# 1_81_Greyscale_OLED_Breakout.net
KiCad netlist of a schematic drawn in EAGLE
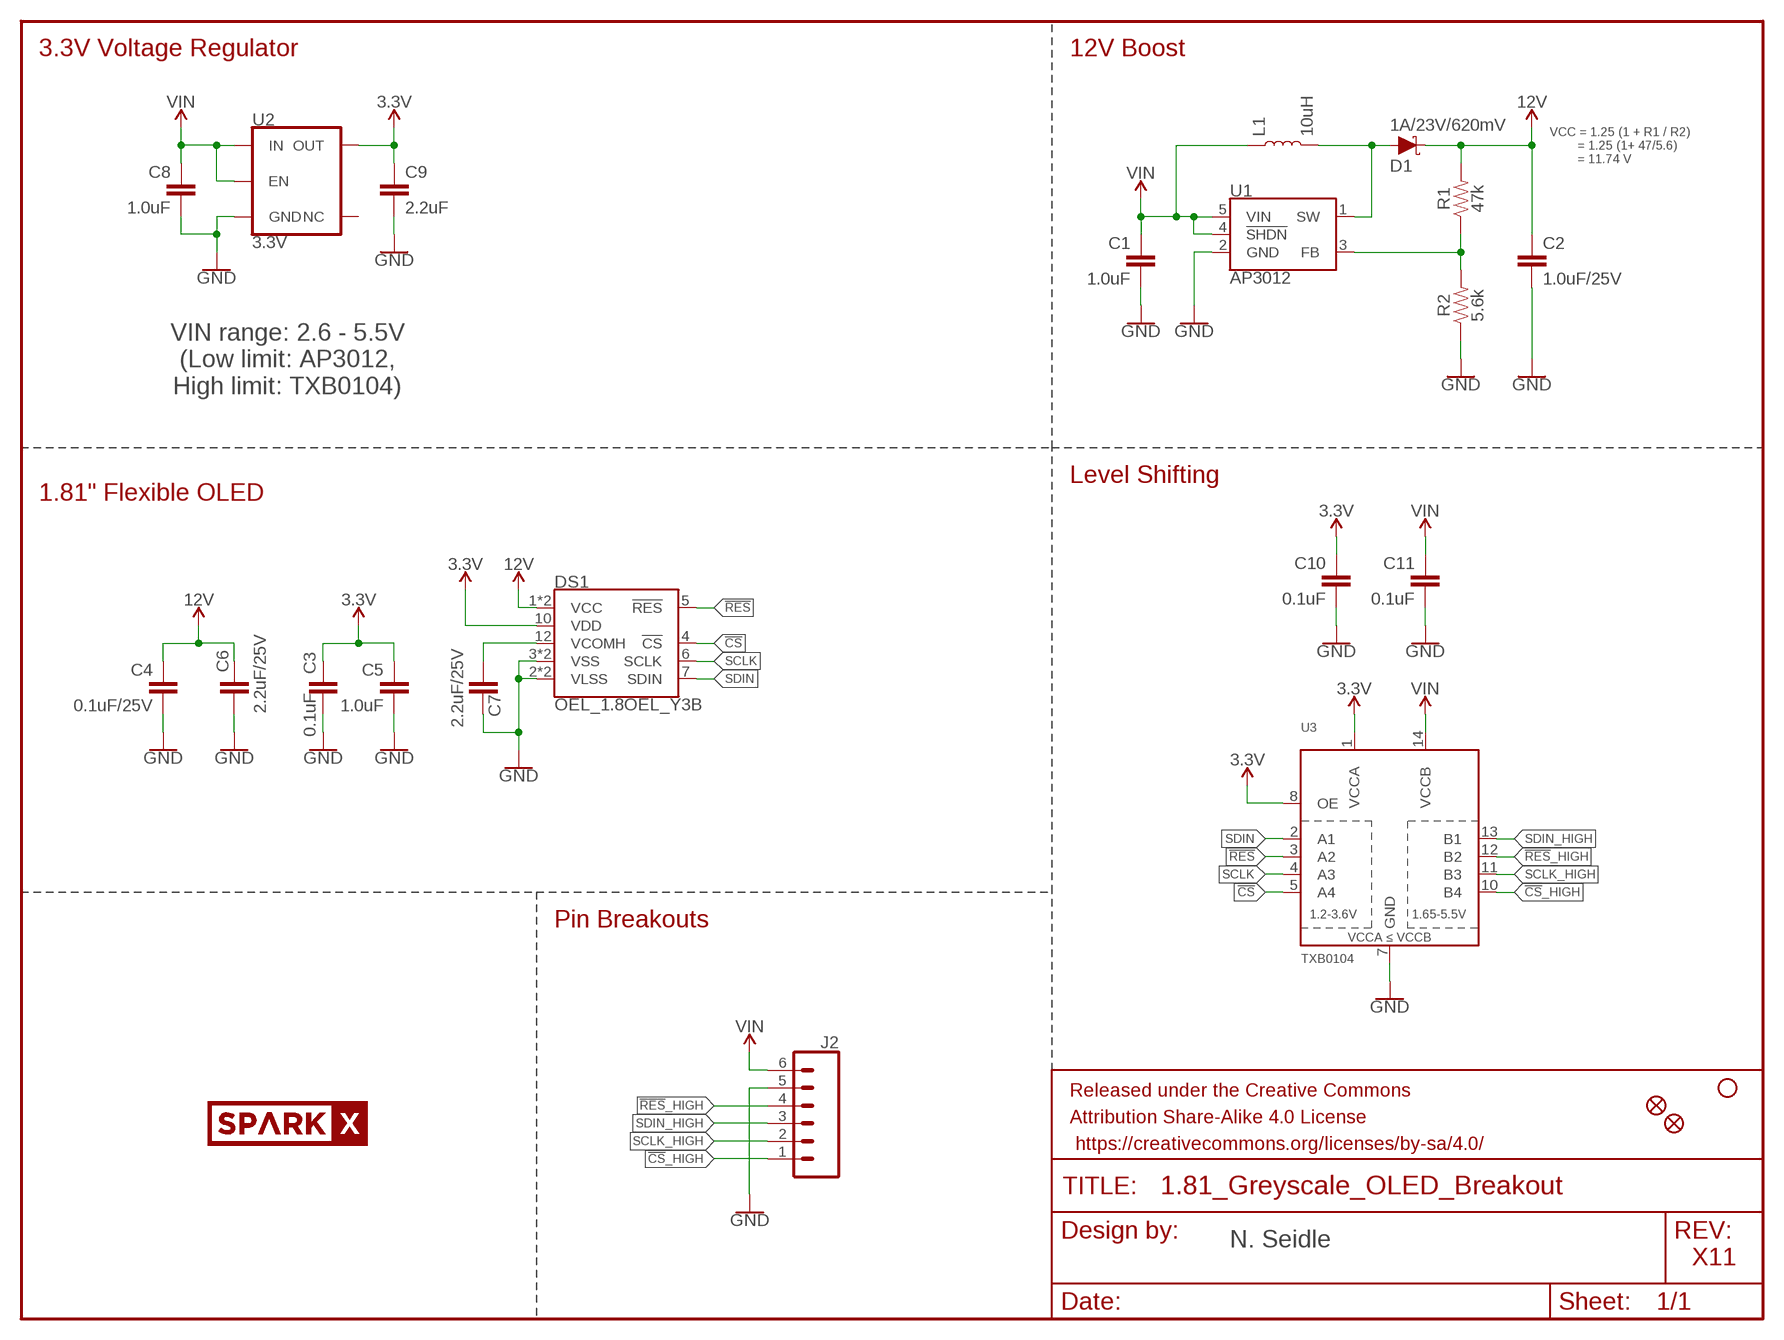
[diagram p0: schematic, sheet 1]

(export (version "E")
  (design (tool "Eeschema 10.0.6"))
  (components
    (comp (ref "C1")
      (value "1.0uF")
      (footprint "eagle-import:0603")
      (libsource (lib "eagle-import") (part "1.0UF-0603-16V-10%"))
    )
    (comp (ref "C2")
      (value "1.0uF/25V")
      (footprint "eagle-import:0805")
      (libsource (lib "eagle-import") (part "1.0UF-0805-25V-(+80/-20%)"))
    )
    (comp (ref "C3")
      (value "0.1uF")
      (footprint "eagle-import:0603")
      (libsource (lib "eagle-import") (part "0.1UF-0603-25V-(+80/-20%)"))
    )
    (comp (ref "C4")
      (value "0.1uF/25V")
      (footprint "eagle-import:0603")
      (libsource (lib "eagle-import") (part "0.1UF-0603-25V-(+80/-20%)"))
    )
    (comp (ref "C5")
      (value "1.0uF")
      (footprint "eagle-import:0603")
      (libsource (lib "eagle-import") (part "1.0UF-0603-16V-10%"))
    )
    (comp (ref "C6")
      (value "2.2uF/25V")
      (footprint "eagle-import:0805")
      (libsource (lib "eagle-import") (part "2.2UF-0805-25V-(+80/-20%)"))
    )
    (comp (ref "C7")
      (value "2.2uF/25V")
      (footprint "eagle-import:0805")
      (libsource (lib "eagle-import") (part "2.2UF-0805-25V-(+80/-20%)"))
    )
    (comp (ref "C8")
      (value "1.0uF")
      (footprint "eagle-import:0603")
      (libsource (lib "eagle-import") (part "1.0UF-0603-16V-10%"))
    )
    (comp (ref "C9")
      (value "2.2uF")
      (footprint "eagle-import:0603")
      (libsource (lib "eagle-import") (part "2.2UF-0603-10V-20%"))
    )
    (comp (ref "C10")
      (value "0.1uF")
      (footprint "eagle-import:0603")
      (libsource (lib "eagle-import") (part "0.1UF-0603-25V-(+80/-20%)"))
    )
    (comp (ref "C11")
      (value "0.1uF")
      (footprint "eagle-import:0603")
      (libsource (lib "eagle-import") (part "0.1UF-0603-25V-(+80/-20%)"))
    )
    (comp (ref "D1")
      (value "1A/23V/620mV")
      (footprint "eagle-import:SOD-323")
      (libsource (lib "eagle-import") (part "DIODE-SCHOTTKY-BAT20J"))
    )
    (comp (ref "DS1")
      (value "OEL_1.8OEL_Y3B")
      (footprint "eagle-import:OEL_1.8_FPC_Y3B")
      (libsource (lib "eagle-import") (part "OEL_1.8OEL_Y3B"))
    )
    (comp (ref "FD1")
      (value "FIDUCIAL1X2")
      (footprint "eagle-import:FIDUCIAL-1X2")
      (libsource (lib "eagle-import") (part "FIDUCIAL1X2"))
    )
    (comp (ref "FD2")
      (value "FIDUCIAL1X2")
      (footprint "eagle-import:FIDUCIAL-1X2")
      (libsource (lib "eagle-import") (part "FIDUCIAL1X2"))
    )
    (comp (ref "FRAME1")
      (value "FRAME-LETTER")
      (footprint "eagle-import:CREATIVE_COMMONS")
      (libsource (lib "eagle-import") (part "FRAME-LETTER"))
    )
    (comp (ref "H2")
      (value "STAND-OFF")
      (footprint "eagle-import:STAND-OFF")
      (libsource (lib "eagle-import") (part "STAND-OFF"))
    )
    (comp (ref "J2")
      (value "CONN_06NO_SILK_NO_POP")
      (footprint "eagle-import:1X06_NO_SILK")
      (libsource (lib "eagle-import") (part "CONN_06NO_SILK_NO_POP"))
    )
    (comp (ref "L1")
      (value "10uH")
      (footprint "eagle-import:INDUCTOR_3X3")
      (libsource (lib "eagle-import") (part "INDUCTORINDUCTOR_10UH"))
    )
    (comp (ref "LOGO1")
      (value "SPARKX-LOGO5")
      (footprint "eagle-import:SPARKX-LARGE")
      (libsource (lib "eagle-import") (part "SPARKX-LOGO5"))
    )
    (comp (ref "R1")
      (value "47k")
      (footprint "eagle-import:0603")
      (libsource (lib "eagle-import") (part "47KOHM-0603-1/10W-1%"))
    )
    (comp (ref "R2")
      (value "5.6k")
      (footprint "eagle-import:0603")
      (libsource (lib "eagle-import") (part "5.6KOHM-0603-1/10W-1%"))
    )
    (comp (ref "U1")
      (value "AP3012")
      (footprint "eagle-import:SOT23-5")
      (libsource (lib "eagle-import") (part "AP3012"))
    )
    (comp (ref "U2")
      (value "3.3V")
      (footprint "eagle-import:SOT23-5")
      (libsource (lib "eagle-import") (part "V_REG_AP2112K-3.3V"))
    )
    (comp (ref "U3")
      (value "TXB0104")
      (footprint "eagle-import:SO14")
      (libsource (lib "eagle-import") (part "TXB0104PWRSOIC14"))
    )
  )
  (nets
    (net (code "1") (name "/~{CS}") (class "Default")
      (node (ref "DS1") (pin "4") (pinfunction "~{CS}_4") (pintype "bidirectional"))
      (node (ref "U3") (pin "5") (pinfunction "A4_5") (pintype "bidirectional"))
    )
    (net (code "2") (name "/~{CS}_HIGH") (class "Default")
      (node (ref "J2") (pin "1") (pinfunction "1_1") (pintype "passive"))
      (node (ref "U3") (pin "10") (pinfunction "B4_10") (pintype "bidirectional"))
    )
    (net (code "3") (name "/~{RES}") (class "Default")
      (node (ref "DS1") (pin "5") (pinfunction "~{RES}_5") (pintype "bidirectional"))
      (node (ref "U3") (pin "3") (pinfunction "A2_3") (pintype "bidirectional"))
    )
    (net (code "4") (name "/~{RES}_HIGH") (class "Default")
      (node (ref "J2") (pin "4") (pinfunction "4_4") (pintype "passive"))
      (node (ref "U3") (pin "12") (pinfunction "B2_12") (pintype "bidirectional"))
    )
    (net (code "5") (name "3.3V") (class "Default")
      (node (ref "C10") (pin "1") (pinfunction "1_1") (pintype "passive"))
      (node (ref "C3") (pin "1") (pinfunction "1_1") (pintype "passive"))
      (node (ref "C5") (pin "1") (pinfunction "1_1") (pintype "passive"))
      (node (ref "C9") (pin "1") (pinfunction "1_1") (pintype "passive"))
      (node (ref "DS1") (pin "10") (pinfunction "VDD_10") (pintype "bidirectional"))
      (node (ref "U2") (pin "5") (pinfunction "OUT_5") (pintype "passive"))
      (node (ref "U3") (pin "1") (pinfunction "VCCA_1") (pintype "bidirectional"))
      (node (ref "U3") (pin "8") (pinfunction "OE_8") (pintype "bidirectional"))
    )
    (net (code "6") (name "12V") (class "Default")
      (node (ref "C2") (pin "1") (pinfunction "1_1") (pintype "passive"))
      (node (ref "C4") (pin "1") (pinfunction "1_1") (pintype "passive"))
      (node (ref "C6") (pin "1") (pinfunction "1_1") (pintype "passive"))
      (node (ref "D1") (pin "C") (pinfunction "C_C") (pintype "passive"))
      (node (ref "DS1") (pin "1") (pinfunction "VCC_1") (pintype "bidirectional"))
      (node (ref "DS1") (pin "13") (pinfunction "VCC_13") (pintype "bidirectional"))
      (node (ref "R1") (pin "2") (pinfunction "2_2") (pintype "passive"))
    )
    (net (code "7") (name "GND") (class "Default")
      (node (ref "C1") (pin "2") (pinfunction "2_2") (pintype "passive"))
      (node (ref "C10") (pin "2") (pinfunction "2_2") (pintype "passive"))
      (node (ref "C11") (pin "2") (pinfunction "2_2") (pintype "passive"))
      (node (ref "C2") (pin "2") (pinfunction "2_2") (pintype "passive"))
      (node (ref "C3") (pin "2") (pinfunction "2_2") (pintype "passive"))
      (node (ref "C4") (pin "2") (pinfunction "2_2") (pintype "passive"))
      (node (ref "C5") (pin "2") (pinfunction "2_2") (pintype "passive"))
      (node (ref "C6") (pin "2") (pinfunction "2_2") (pintype "passive"))
      (node (ref "C7") (pin "1") (pinfunction "1_1") (pintype "passive"))
      (node (ref "C8") (pin "2") (pinfunction "2_2") (pintype "passive"))
      (node (ref "C9") (pin "2") (pinfunction "2_2") (pintype "passive"))
      (node (ref "DS1") (pin "2") (pinfunction "VLSS_2") (pintype "bidirectional"))
      (node (ref "DS1") (pin "3") (pinfunction "VSS_3") (pintype "bidirectional"))
      (node (ref "DS1") (pin "8") (pinfunction "VSS_8") (pintype "bidirectional"))
      (node (ref "DS1") (pin "9") (pinfunction "VLSS_9") (pintype "bidirectional"))
      (node (ref "J2") (pin "5") (pinfunction "5_5") (pintype "passive"))
      (node (ref "R2") (pin "1") (pinfunction "1_1") (pintype "passive"))
      (node (ref "U1") (pin "2") (pinfunction "GND_2") (pintype "bidirectional"))
      (node (ref "U2") (pin "2") (pinfunction "GND_2") (pintype "input"))
      (node (ref "U3") (pin "7") (pinfunction "GND_7") (pintype "bidirectional"))
    )
    (net (code "8") (name "Net-(DS1-VCOMH)") (class "Default")
      (node (ref "C7") (pin "2") (pinfunction "2_2") (pintype "passive"))
      (node (ref "DS1") (pin "12") (pinfunction "VCOMH_12") (pintype "bidirectional"))
    )
    (net (code "9") (name "Net-(L1-2)") (class "Default")
      (node (ref "D1") (pin "A") (pinfunction "A_A") (pintype "passive"))
      (node (ref "L1") (pin "P$2") (pinfunction "2_P$2") (pintype "passive"))
      (node (ref "U1") (pin "1") (pinfunction "SW_1") (pintype "bidirectional"))
    )
    (net (code "10") (name "Net-(U1-FB)") (class "Default")
      (node (ref "R1") (pin "1") (pinfunction "1_1") (pintype "passive"))
      (node (ref "R2") (pin "2") (pinfunction "2_2") (pintype "passive"))
      (node (ref "U1") (pin "3") (pinfunction "FB_3") (pintype "bidirectional"))
    )
    (net (code "11") (name "SCLK") (class "Default")
      (node (ref "DS1") (pin "6") (pinfunction "SCLK_6") (pintype "bidirectional"))
      (node (ref "U3") (pin "4") (pinfunction "A3_4") (pintype "bidirectional"))
    )
    (net (code "12") (name "SCLK_HIGH") (class "Default")
      (node (ref "J2") (pin "2") (pinfunction "2_2") (pintype "passive"))
      (node (ref "U3") (pin "11") (pinfunction "B3_11") (pintype "bidirectional"))
    )
    (net (code "13") (name "SDIN") (class "Default")
      (node (ref "DS1") (pin "7") (pinfunction "SDIN_7") (pintype "bidirectional"))
      (node (ref "U3") (pin "2") (pinfunction "A1_2") (pintype "bidirectional"))
    )
    (net (code "14") (name "SDIN_HIGH") (class "Default")
      (node (ref "J2") (pin "3") (pinfunction "3_3") (pintype "passive"))
      (node (ref "U3") (pin "13") (pinfunction "B1_13") (pintype "bidirectional"))
    )
    (net (code "15") (name "VIN") (class "Default")
      (node (ref "C1") (pin "1") (pinfunction "1_1") (pintype "passive"))
      (node (ref "C11") (pin "1") (pinfunction "1_1") (pintype "passive"))
      (node (ref "C8") (pin "1") (pinfunction "1_1") (pintype "passive"))
      (node (ref "J2") (pin "6") (pinfunction "6_6") (pintype "passive"))
      (node (ref "L1") (pin "P$1") (pinfunction "1_P$1") (pintype "passive"))
      (node (ref "U1") (pin "4") (pinfunction "~{SHDN}_4") (pintype "bidirectional"))
      (node (ref "U1") (pin "5") (pinfunction "VIN_5") (pintype "bidirectional"))
      (node (ref "U2") (pin "1") (pinfunction "IN_1") (pintype "input"))
      (node (ref "U2") (pin "3") (pinfunction "EN_3") (pintype "input"))
      (node (ref "U3") (pin "14") (pinfunction "VCCB_14") (pintype "bidirectional"))
    )
    (net (code "16") (name "unconnected-(U2-NC-Pad4)") (class "Default")
      (node (ref "U2") (pin "4") (pinfunction "NC_4") (pintype "no_connect"))
    )
  )
)
